# SCH_FinallyPCB_CARD_2024-10-10.net
KiCad netlist of a schematic drawn in EasyEDA
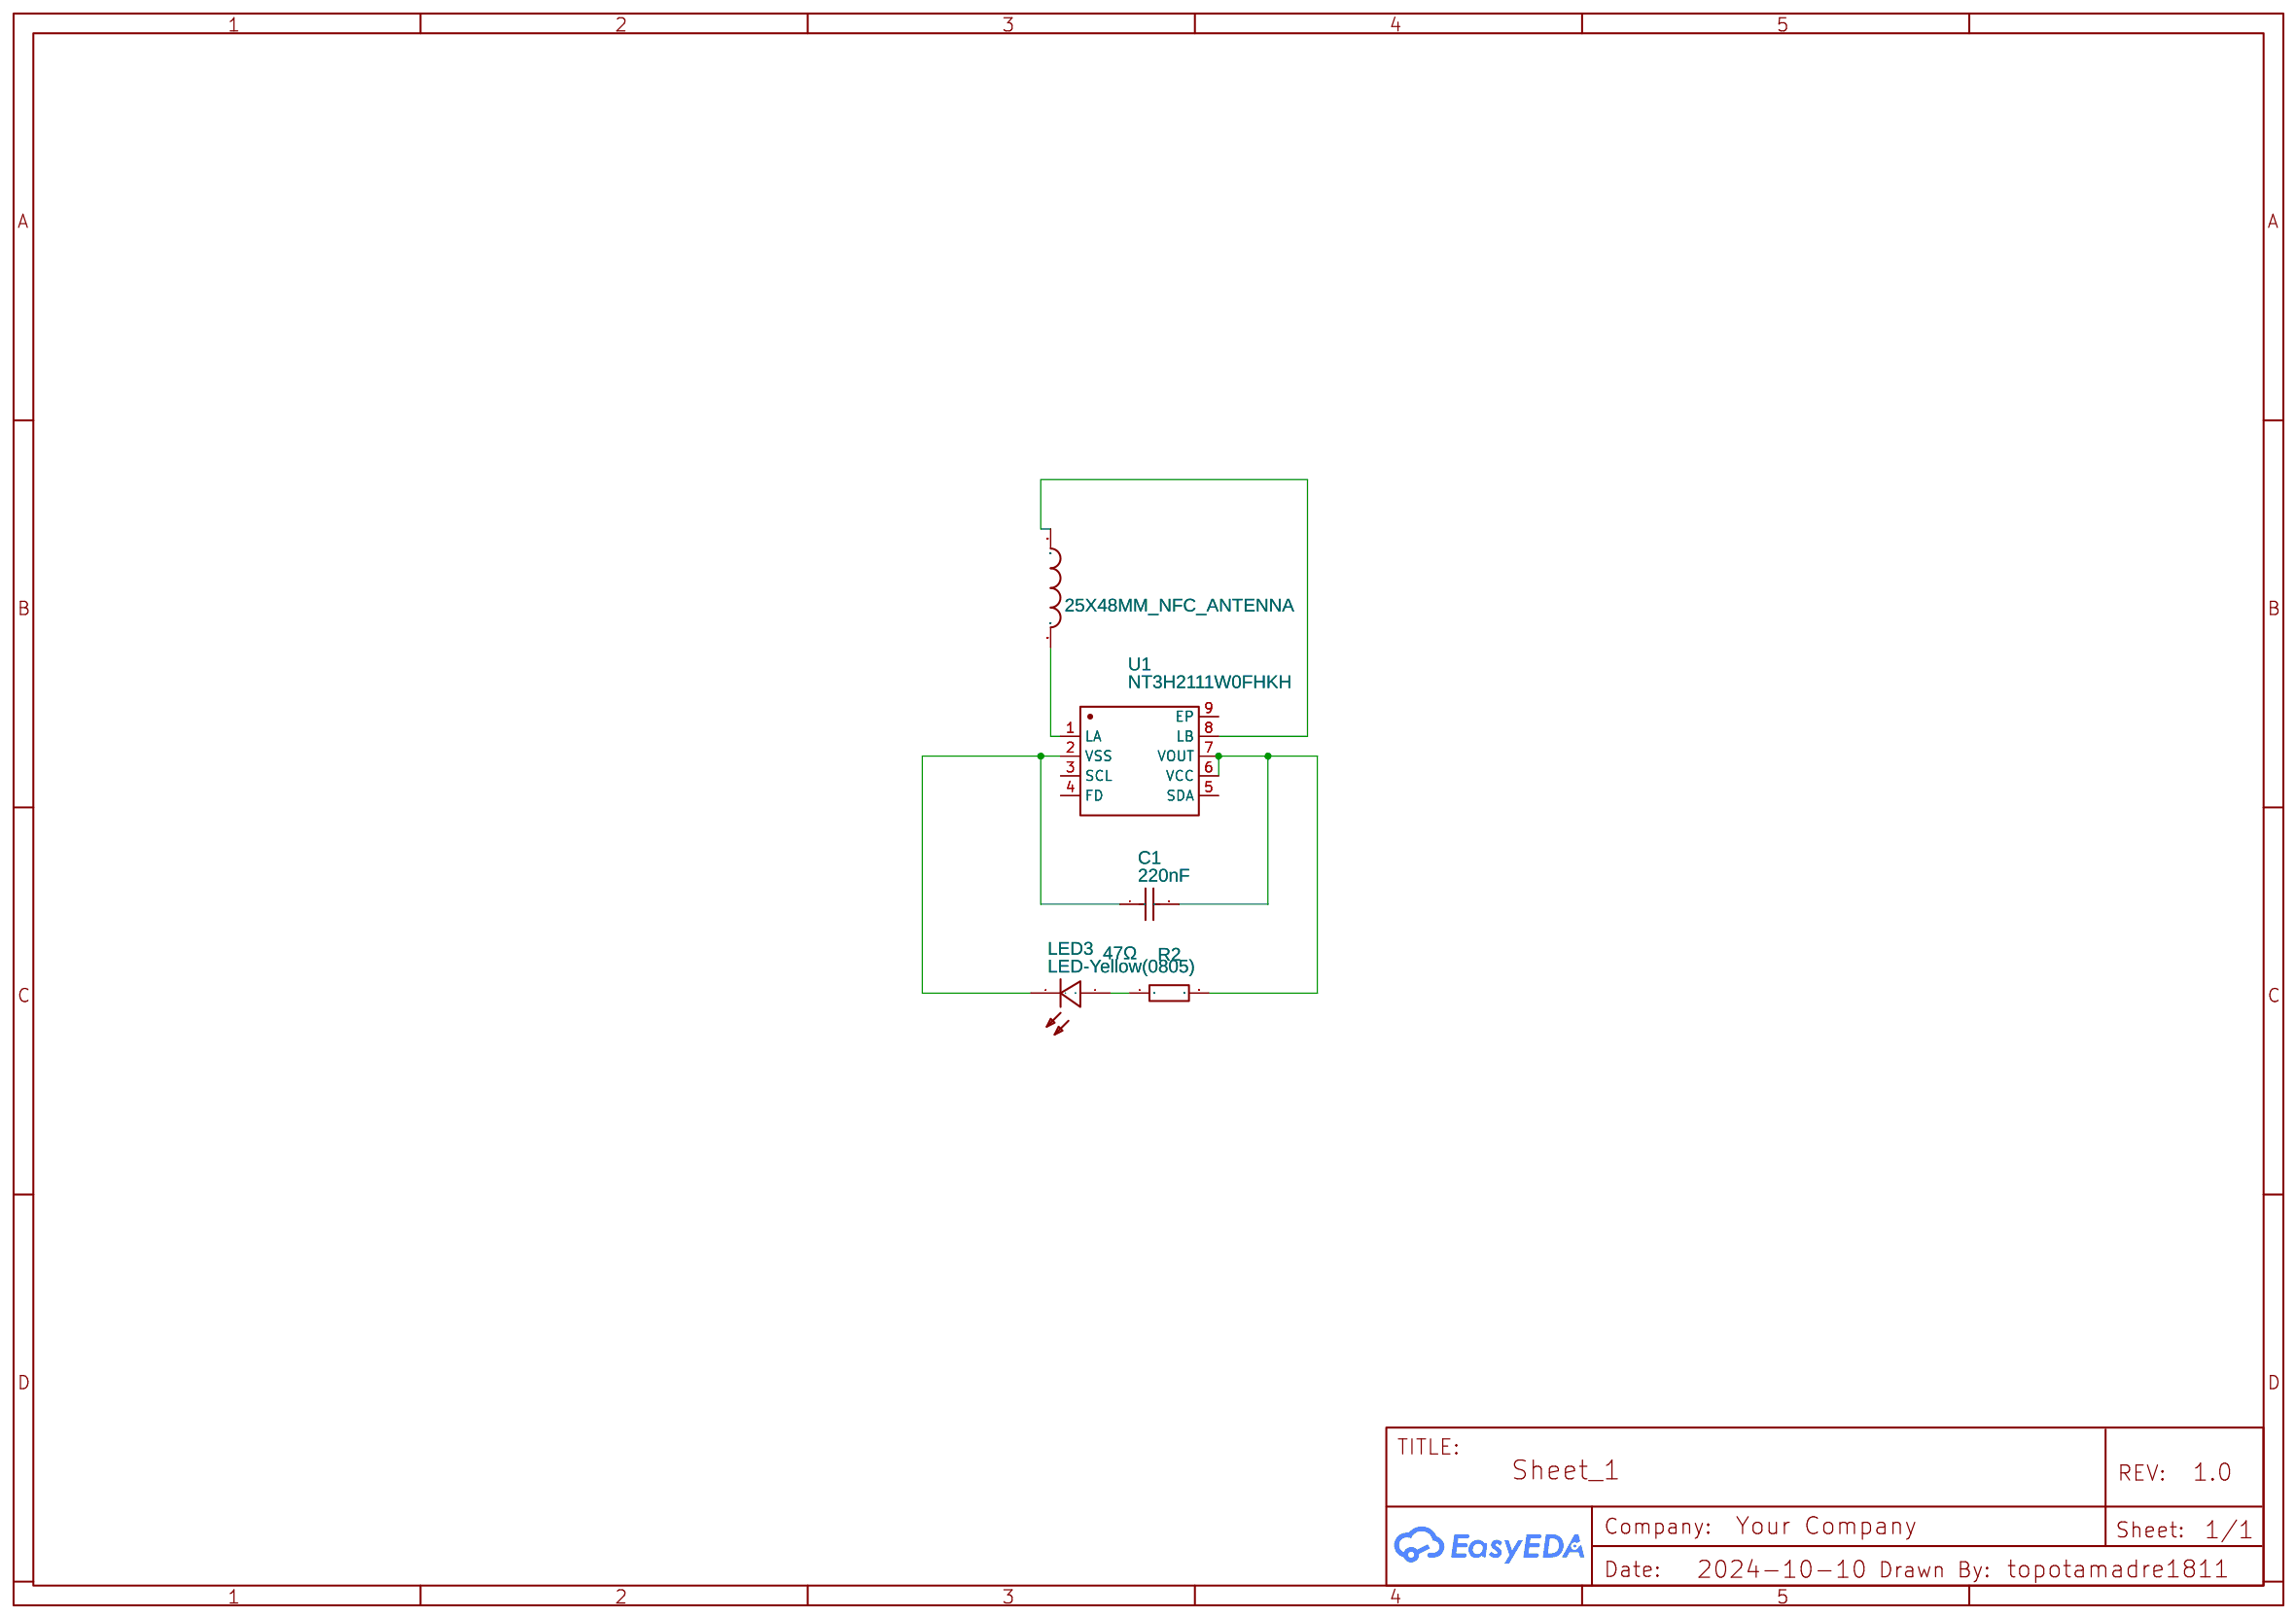
[diagram p0: schematic sheet]

(export (version "E")
  (design (tool "Eeschema 10.0.6"))
  (components
    (comp (ref "1") (value "25X48MM_NFC_ANTENNA") (libsource (lib "") (part "25X48MM_NFC_ANTENNA")))
    (comp (ref "C1")
      (value "220nF")
      (fields
        (field (name "Manufacturer Part") "CL10B224KA8NNNC")
        (field (name "Manufacturer") "SAMSUNG(三星)")
      )
      (libsource (lib "") (part "CL10B224KA8NNNC"))
    )
    (comp (ref "LED3")
      (value "LED-Yellow(0805)")
      (fields
        (field (name "Manufacturer Part") "17-21SUYC/TR8")
        (field (name "Manufacturer") "Hubei KENTO Elec")
      )
      (libsource (lib "") (part "LED-Yellow(0805)"))
    )
    (comp (ref "R2")
      (value "47Ω")
      (fields
        (field (name "Manufacturer Part") "0603WAF470JT5E")
        (field (name "Manufacturer") "UNI-ROYAL(厚声)")
      )
      (libsource (lib "") (part "0603WAF470JT5E"))
    )
    (comp (ref "U1")
      (value "NT3H2111W0FHKH")
      (fields (field (name "Manufacturer") "NXP(恩智浦)"))
      (libsource (lib "") (part "NT3H2111W0FHKH"))
    )
  )
  (nets
    (net (code "1") (name "Net-(LED3-+)") (class "Default")
      (node (ref "LED3") (pin "1") (pinfunction "+_1") (pintype "unspecified"))
      (node (ref "R2") (pin "1") (pinfunction "1_1") (pintype "input"))
    )
    (net (code "2") (name "Net-(LED3--)") (class "Default")
      (node (ref "C1") (pin "1") (pinfunction "1_1") (pintype "input"))
      (node (ref "LED3") (pin "2") (pinfunction "-_2") (pintype "unspecified"))
      (node (ref "U1") (pin "2") (pinfunction "VSS_2") (pintype "unspecified"))
    )
    (net (code "3") (name "Net-(U1-LA)") (class "Default")
      (node (ref "1") (pin "P$2") (pinfunction "P$2_P$2") (pintype "bidirectional"))
      (node (ref "U1") (pin "1") (pinfunction "LA_1") (pintype "unspecified"))
    )
    (net (code "4") (name "Net-(U1-LB)") (class "Default")
      (node (ref "1") (pin "P$1") (pinfunction "P$1_P$1") (pintype "bidirectional"))
      (node (ref "U1") (pin "8") (pinfunction "LB_8") (pintype "unspecified"))
    )
    (net (code "5") (name "Net-(U1-VCC)") (class "Default")
      (node (ref "C1") (pin "2") (pinfunction "2_2") (pintype "input"))
      (node (ref "R2") (pin "2") (pinfunction "2_2") (pintype "input"))
      (node (ref "U1") (pin "6") (pinfunction "VCC_6") (pintype "unspecified"))
      (node (ref "U1") (pin "7") (pinfunction "VOUT_7") (pintype "unspecified"))
    )
    (net (code "6") (name "unconnected-(U1-EP-Pad9)") (class "Default")
      (node (ref "U1") (pin "9") (pinfunction "EP_9") (pintype "unspecified"))
    )
    (net (code "7") (name "unconnected-(U1-FD-Pad4)") (class "Default")
      (node (ref "U1") (pin "4") (pinfunction "FD_4") (pintype "unspecified"))
    )
    (net (code "8") (name "unconnected-(U1-SCL-Pad3)") (class "Default")
      (node (ref "U1") (pin "3") (pinfunction "SCL_3") (pintype "unspecified"))
    )
    (net (code "9") (name "unconnected-(U1-SDA-Pad5)") (class "Default")
      (node (ref "U1") (pin "5") (pinfunction "SDA_5") (pintype "unspecified"))
    )
  )
)
